# design1.net
KiCad netlist of a schematic drawn in EAGLE
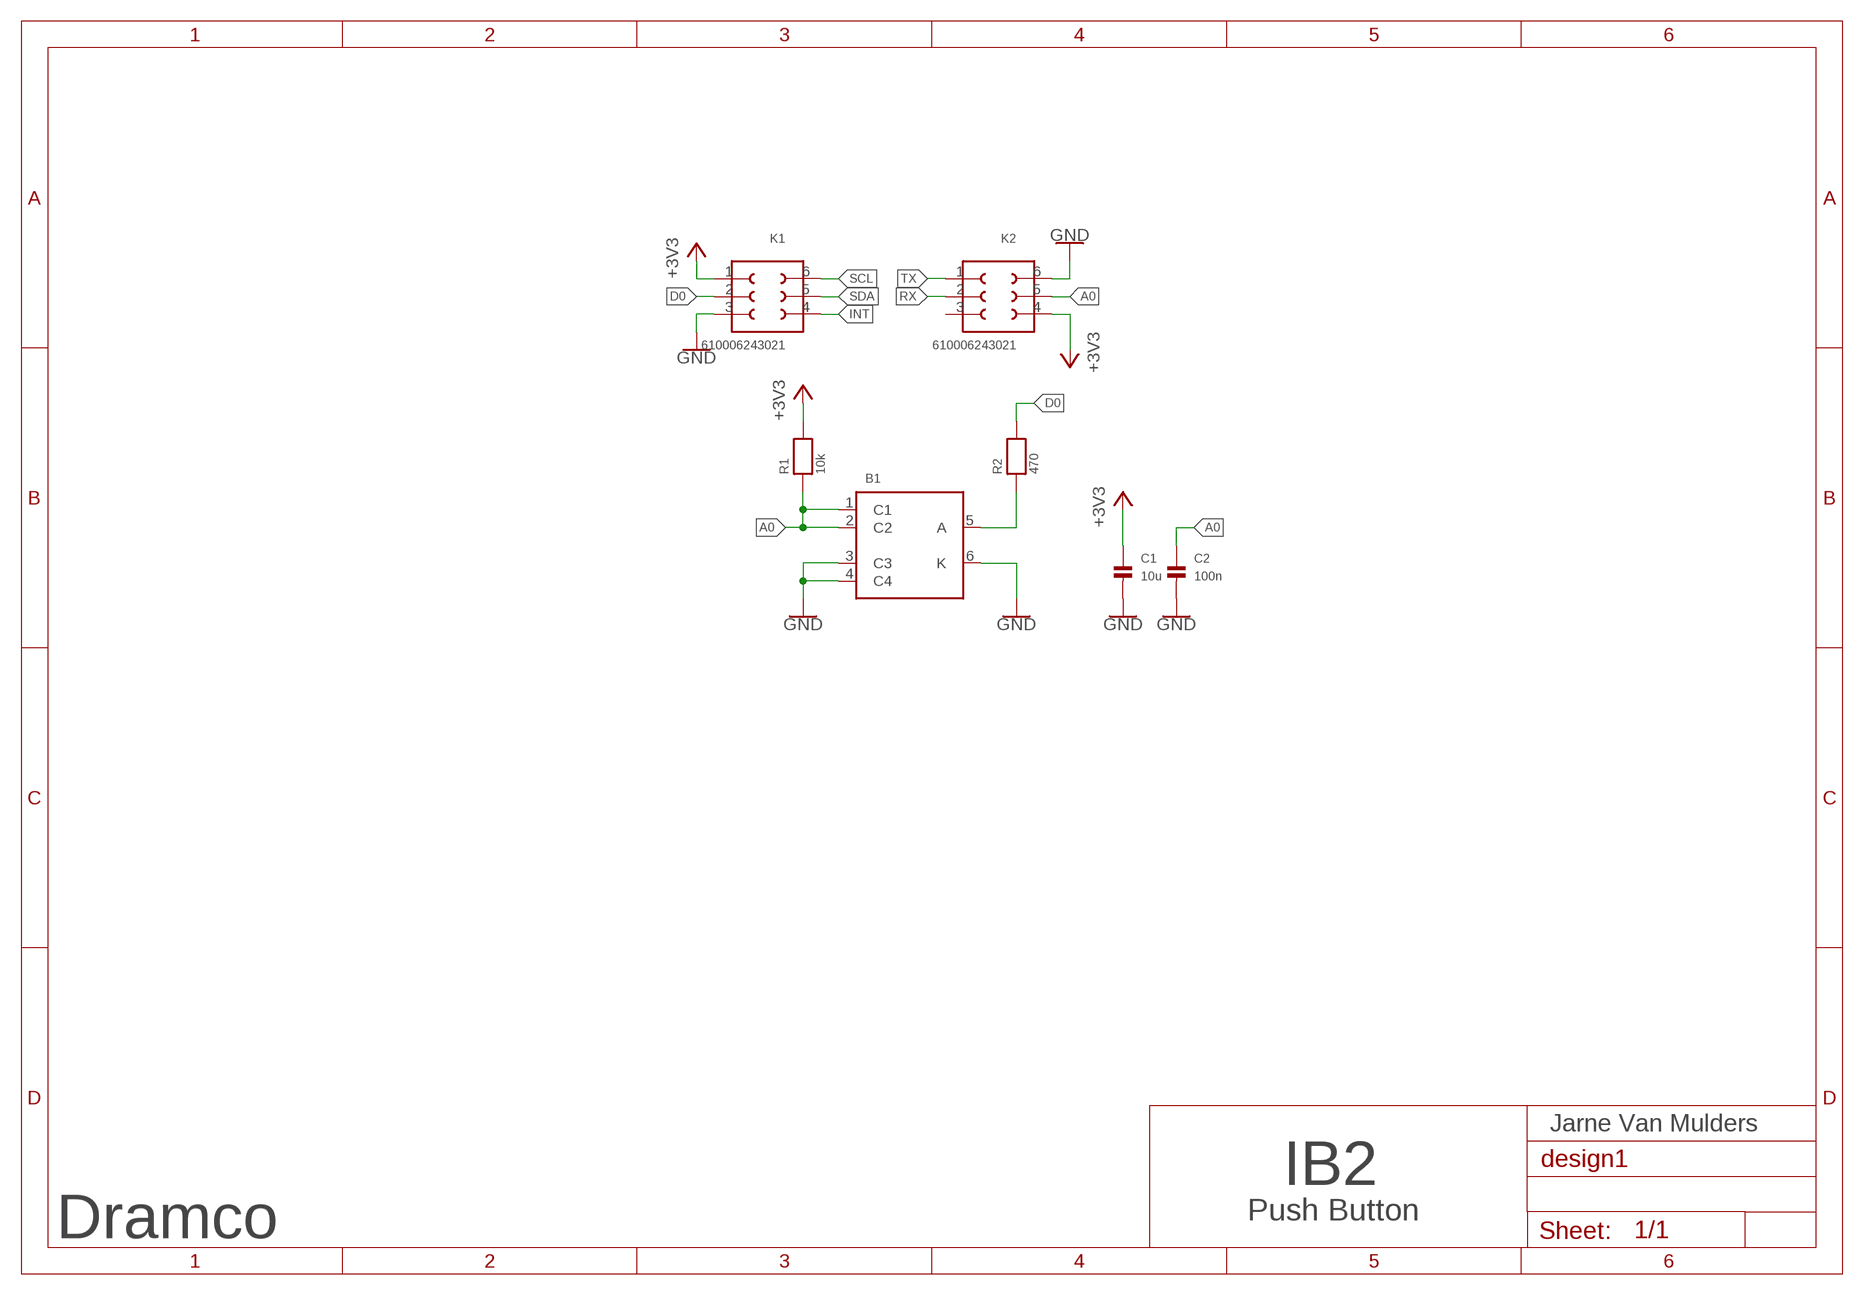
[diagram p0: schematic, sheet 1]

(export (version "E")
  (design (tool "Eeschema 10.0.6"))
  (components
    (comp (ref "B1")
      (value "TS121273_AKSMD")
      (footprint "eagle-import:TS121273_AKSMD")
      (libsource (lib "eagle-import") (part "TS121273_AKSMD"))
    )
    (comp (ref "C1")
      (value "10u")
      (footprint "eagle-import:0805")
      (libsource (lib "eagle-import") (part "CAP_CERAMIC0805"))
    )
    (comp (ref "C2")
      (value "100n")
      (footprint "eagle-import:0603")
      (libsource (lib "eagle-import") (part "CAP_CERAMIC0603"))
    )
    (comp (ref "K1")
      (value "610006243021")
      (footprint "eagle-import:610006243021")
      (libsource (lib "eagle-import") (part "610006243021"))
    )
    (comp (ref "K2")
      (value "610006243021")
      (footprint "eagle-import:610006243021")
      (libsource (lib "eagle-import") (part "610006243021"))
    )
    (comp (ref "R1")
      (value "10k")
      (footprint "eagle-import:0603")
      (libsource (lib "eagle-import") (part "RESISTOR0603"))
    )
    (comp (ref "R2")
      (value "470")
      (footprint "eagle-import:0603")
      (libsource (lib "eagle-import") (part "RESISTOR0603"))
    )
  )
  (nets
    (net (code "1") (name "+3V3") (class "Default")
      (node (ref "C1") (pin "1") (pinfunction "P$1_1") (pintype "passive"))
      (node (ref "K1") (pin "1") (pinfunction "1_1") (pintype "passive"))
      (node (ref "K2") (pin "4") (pinfunction "4_4") (pintype "passive"))
      (node (ref "R1") (pin "2") (pinfunction "2_2") (pintype "passive"))
    )
    (net (code "2") (name "A0") (class "Default")
      (node (ref "B1") (pin "1") (pinfunction "C1_1") (pintype "bidirectional"))
      (node (ref "B1") (pin "2") (pinfunction "C2_2") (pintype "bidirectional"))
      (node (ref "C2") (pin "1") (pinfunction "P$1_1") (pintype "passive"))
      (node (ref "K2") (pin "5") (pinfunction "5_5") (pintype "passive"))
      (node (ref "R1") (pin "1") (pinfunction "1_1") (pintype "passive"))
    )
    (net (code "3") (name "D0") (class "Default")
      (node (ref "K1") (pin "2") (pinfunction "2_2") (pintype "passive"))
      (node (ref "R2") (pin "2") (pinfunction "2_2") (pintype "passive"))
    )
    (net (code "4") (name "GND") (class "Default")
      (node (ref "B1") (pin "3") (pinfunction "C3_3") (pintype "bidirectional"))
      (node (ref "B1") (pin "4") (pinfunction "C4_4") (pintype "bidirectional"))
      (node (ref "B1") (pin "6") (pinfunction "K_6") (pintype "bidirectional"))
      (node (ref "C1") (pin "2") (pinfunction "P$2_2") (pintype "passive"))
      (node (ref "C2") (pin "2") (pinfunction "P$2_2") (pintype "passive"))
      (node (ref "K1") (pin "3") (pinfunction "3_3") (pintype "passive"))
      (node (ref "K2") (pin "6") (pinfunction "6_6") (pintype "passive"))
    )
    (net (code "5") (name "INT") (class "Default")
      (node (ref "K1") (pin "4") (pinfunction "4_4") (pintype "passive"))
    )
    (net (code "6") (name "Net-(B1-A)") (class "Default")
      (node (ref "B1") (pin "5") (pinfunction "A_5") (pintype "bidirectional"))
      (node (ref "R2") (pin "1") (pinfunction "1_1") (pintype "passive"))
    )
    (net (code "7") (name "RX") (class "Default")
      (node (ref "K2") (pin "2") (pinfunction "2_2") (pintype "passive"))
    )
    (net (code "8") (name "SCL") (class "Default")
      (node (ref "K1") (pin "6") (pinfunction "6_6") (pintype "passive"))
    )
    (net (code "9") (name "SDA") (class "Default")
      (node (ref "K1") (pin "5") (pinfunction "5_5") (pintype "passive"))
    )
    (net (code "10") (name "TX") (class "Default")
      (node (ref "K2") (pin "1") (pinfunction "1_1") (pintype "passive"))
    )
    (net (code "11") (name "unconnected-(K2-Pad3)") (class "Default")
      (node (ref "K2") (pin "3") (pinfunction "3_3") (pintype "passive"))
    )
  )
)
